# nodoSensorXbee_v3_2.net
KiCad netlist of a schematic drawn in EAGLE
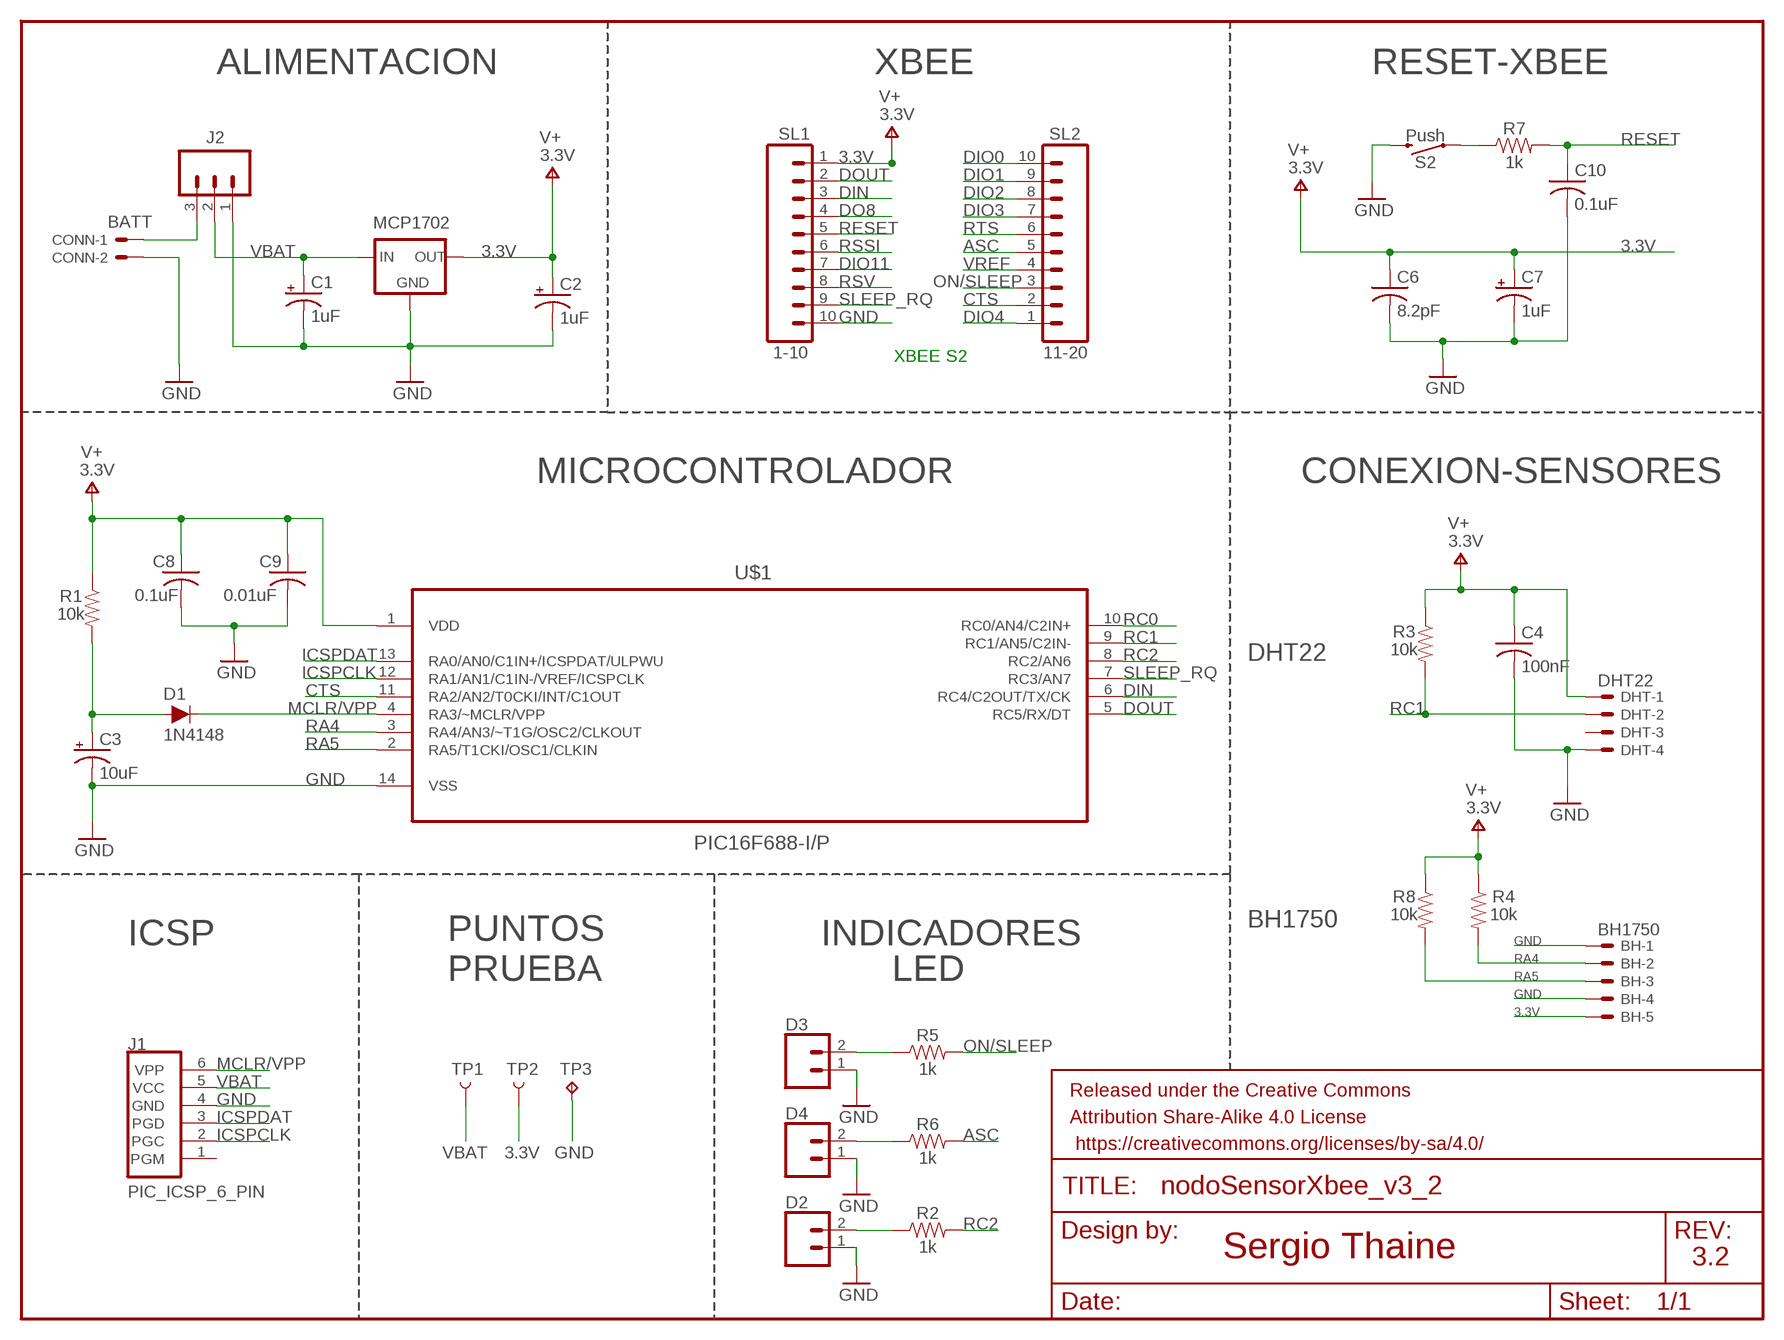
[diagram p0: schematic, sheet 1]

(export (version "E")
  (design (tool "Eeschema 10.0.6"))
  (components
    (comp (ref "BH")
      (value "BH1750")
      (footprint "eagle-import:6410-05")
      (libsource (lib "eagle-import") (part "22-?-0527-2051"))
    )
    (comp (ref "C1")
      (value "1uF")
      (footprint "eagle-import:E2-5")
      (libsource (lib "eagle-import") (part "CPOL-USE2-5"))
    )
    (comp (ref "C2")
      (value "1uF")
      (footprint "eagle-import:E2-5")
      (libsource (lib "eagle-import") (part "CPOL-USE2-5"))
    )
    (comp (ref "C3")
      (value "10uF")
      (footprint "eagle-import:E2-5")
      (libsource (lib "eagle-import") (part "CPOL-USE2-5"))
    )
    (comp (ref "C4")
      (value "100nF")
      (footprint "eagle-import:C025-030X050")
      (libsource (lib "eagle-import") (part "C-US025-030X050"))
    )
    (comp (ref "C6")
      (value "8.2pF")
      (footprint "eagle-import:C025-030X050")
      (libsource (lib "eagle-import") (part "C-US025-030X050"))
    )
    (comp (ref "C7")
      (value "1uF")
      (footprint "eagle-import:E2-5")
      (libsource (lib "eagle-import") (part "CPOL-USE2-5"))
    )
    (comp (ref "C8")
      (value "0.1uF")
      (footprint "eagle-import:C025-030X050")
      (libsource (lib "eagle-import") (part "C-US025-030X050"))
    )
    (comp (ref "C9")
      (value "0.01uF")
      (footprint "eagle-import:C025-030X050")
      (libsource (lib "eagle-import") (part "C-US025-030X050"))
    )
    (comp (ref "C10")
      (value "0.1uF")
      (footprint "eagle-import:C025-030X050")
      (libsource (lib "eagle-import") (part "C-US025-030X050"))
    )
    (comp (ref "CONN")
      (value "BATT")
      (footprint "eagle-import:6410-02")
      (libsource (lib "eagle-import") (part "22-?-0227-2021"))
    )
    (comp (ref "D1")
      (value "1N4148")
      (footprint "eagle-import:DIODE-1N4148")
      (libsource (lib "eagle-import") (part "DIODE-1N4148"))
    )
    (comp (ref "D2")
      (value "CONN_02POLAR")
      (footprint "eagle-import:MOLEX-1X2")
      (libsource (lib "eagle-import") (part "CONN_02POLAR"))
    )
    (comp (ref "D3")
      (value "CONN_02POLAR")
      (footprint "eagle-import:MOLEX-1X2")
      (libsource (lib "eagle-import") (part "CONN_02POLAR"))
    )
    (comp (ref "D4")
      (value "CONN_02POLAR")
      (footprint "eagle-import:MOLEX-1X2")
      (libsource (lib "eagle-import") (part "CONN_02POLAR"))
    )
    (comp (ref "DHT")
      (value "DHT22")
      (footprint "eagle-import:6410-04")
      (libsource (lib "eagle-import") (part "22-?-0427-2041"))
    )
    (comp (ref "FRAME1")
      (value "FRAME-LETTERNO_PACKAGE")
      (footprint "eagle-import:DUMMY")
      (fields (field (name "DESIGNER") "Nobody"))
      (libsource (lib "eagle-import") (part "FRAME-LETTERNO_PACKAGE"))
    )
    (comp (ref "J1")
      (value "PIC_ICSP_6_PIN")
      (footprint "eagle-import:MOLEX-1X6")
      (libsource (lib "eagle-import") (part "PIC_ICSP_6_PIN"))
    )
    (comp (ref "J2")
      (value "CONN_03POLAR")
      (footprint "eagle-import:MOLEX-1X3")
      (libsource (lib "eagle-import") (part "CONN_03POLAR"))
    )
    (comp (ref "MCP1702")
      (value "3.3v")
      (footprint "eagle-import:TO92")
      (libsource (lib "eagle-import") (part "MCP1700TRI"))
    )
    (comp (ref "R1")
      (value "10k")
      (footprint "eagle-import:AXIAL-0.3-KIT")
      (libsource (lib "eagle-import") (part "10KOHM-HORIZ_KIT-1/4W-1%"))
    )
    (comp (ref "R2")
      (value "1k")
      (footprint "eagle-import:AXIAL-0.3-KIT")
      (libsource (lib "eagle-import") (part "10KOHM-HORIZ_KIT-1/4W-1%"))
    )
    (comp (ref "R3")
      (value "10k")
      (footprint "eagle-import:AXIAL-0.3-KIT")
      (libsource (lib "eagle-import") (part "10KOHM-HORIZ_KIT-1/4W-1%"))
    )
    (comp (ref "R4")
      (value "10k")
      (footprint "eagle-import:AXIAL-0.3-KIT")
      (libsource (lib "eagle-import") (part "10KOHM-HORIZ_KIT-1/4W-1%"))
    )
    (comp (ref "R5")
      (value "1k")
      (footprint "eagle-import:AXIAL-0.3-KIT")
      (libsource (lib "eagle-import") (part "10KOHM-HORIZ_KIT-1/4W-1%"))
    )
    (comp (ref "R6")
      (value "1k")
      (footprint "eagle-import:AXIAL-0.3-KIT")
      (libsource (lib "eagle-import") (part "10KOHM-HORIZ_KIT-1/4W-1%"))
    )
    (comp (ref "R7")
      (value "1k")
      (footprint "eagle-import:AXIAL-0.3-KIT")
      (libsource (lib "eagle-import") (part "10KOHM-HORIZ_KIT-1/4W-1%"))
    )
    (comp (ref "R8")
      (value "10k")
      (footprint "eagle-import:AXIAL-0.3-KIT")
      (libsource (lib "eagle-import") (part "10KOHM-HORIZ_KIT-1/4W-1%"))
    )
    (comp (ref "S2")
      (value "Push")
      (footprint "eagle-import:TACTILE_SWITCH_PTH_6.0MM")
      (libsource (lib "eagle-import") (part "MOMENTARY-SWITCH-SPST-PTH-6.0MM"))
    )
    (comp (ref "SL1")
      (value "1-10")
      (footprint "eagle-import:10P")
      (libsource (lib "eagle-import") (part "M10"))
    )
    (comp (ref "SL2")
      (value "11-20")
      (footprint "eagle-import:10P")
      (libsource (lib "eagle-import") (part "M10"))
    )
    (comp (ref "TP1")
      (value "VBAT")
      (footprint "eagle-import:PAD.03X.05")
      (libsource (lib "eagle-import") (part "TEST-POINT3X5"))
    )
    (comp (ref "TP2")
      (value "3.3V")
      (footprint "eagle-import:PAD.03X.05")
      (libsource (lib "eagle-import") (part "TEST-POINT3X5"))
    )
    (comp (ref "TP3")
      (value "TPPAD1-13")
      (footprint "eagle-import:P1-13")
      (libsource (lib "eagle-import") (part "TPPAD1-13"))
    )
    (comp (ref "U$1")
      (value "PIC16F688-I/P")
      (footprint "eagle-import:DIP254P762X533-14")
      (libsource (lib "eagle-import") (part "PIC16F688-I/P"))
    )
  )
  (nets
    (net (code "1") (name "/ASC") (class "Default")
      (node (ref "R6") (pin "P$2") (pinfunction "2_P$2") (pintype "passive"))
      (node (ref "SL2") (pin "5") (pinfunction "5_5") (pintype "passive"))
    )
    (net (code "2") (name "/CTS") (class "Default")
      (node (ref "SL2") (pin "2") (pinfunction "2_2") (pintype "passive"))
      (node (ref "U$1") (pin "11") (pinfunction "RA2/AN2/T0CKI/INT/C1OUT_11") (pintype "bidirectional"))
    )
    (net (code "3") (name "/DIN") (class "Default")
      (node (ref "SL1") (pin "3") (pinfunction "3_3") (pintype "passive"))
      (node (ref "U$1") (pin "6") (pinfunction "RC4/C2OUT/TX/CK_6") (pintype "bidirectional"))
    )
    (net (code "4") (name "/DIO0") (class "Default")
      (node (ref "SL2") (pin "10") (pinfunction "10_10") (pintype "passive"))
    )
    (net (code "5") (name "/DIO1") (class "Default")
      (node (ref "SL2") (pin "9") (pinfunction "9_9") (pintype "passive"))
    )
    (net (code "6") (name "/DIO2") (class "Default")
      (node (ref "SL2") (pin "8") (pinfunction "8_8") (pintype "passive"))
    )
    (net (code "7") (name "/DIO3") (class "Default")
      (node (ref "SL2") (pin "7") (pinfunction "7_7") (pintype "passive"))
    )
    (net (code "8") (name "/DIO4") (class "Default")
      (node (ref "SL2") (pin "1") (pinfunction "1_1") (pintype "passive"))
    )
    (net (code "9") (name "/DIO11") (class "Default")
      (node (ref "SL1") (pin "7") (pinfunction "7_7") (pintype "passive"))
    )
    (net (code "10") (name "/DO8") (class "Default")
      (node (ref "SL1") (pin "4") (pinfunction "4_4") (pintype "passive"))
    )
    (net (code "11") (name "/DOUT") (class "Default")
      (node (ref "SL1") (pin "2") (pinfunction "2_2") (pintype "passive"))
      (node (ref "U$1") (pin "5") (pinfunction "RC5/RX/DT_5") (pintype "bidirectional"))
    )
    (net (code "12") (name "/ICSPCLK") (class "Default")
      (node (ref "J1") (pin "2") (pinfunction "PGC_2") (pintype "bidirectional"))
      (node (ref "U$1") (pin "12") (pinfunction "RA1/AN1/C1IN-/VREF/ICSPCLK_12") (pintype "bidirectional"))
    )
    (net (code "13") (name "/ICSPDAT") (class "Default")
      (node (ref "J1") (pin "3") (pinfunction "PGD_3") (pintype "bidirectional"))
      (node (ref "U$1") (pin "13") (pinfunction "RA0/AN0/C1IN+/ICSPDAT/ULPWU_13") (pintype "bidirectional"))
    )
    (net (code "14") (name "/MCLR{slash}VPP") (class "Default")
      (node (ref "D1") (pin "C") (pinfunction "C_C") (pintype "passive"))
      (node (ref "J1") (pin "6") (pinfunction "VPP_6") (pintype "bidirectional"))
      (node (ref "U$1") (pin "4") (pinfunction "RA3/~{MCLR/VPP}_4") (pintype "input"))
    )
    (net (code "15") (name "/ON{slash}SLEEP") (class "Default")
      (node (ref "R5") (pin "P$2") (pinfunction "2_P$2") (pintype "passive"))
      (node (ref "SL2") (pin "3") (pinfunction "3_3") (pintype "passive"))
    )
    (net (code "16") (name "/RA4") (class "Default")
      (node (ref "BH") (pin "2") (pinfunction "S_2") (pintype "passive"))
      (node (ref "R4") (pin "P$2") (pinfunction "2_P$2") (pintype "passive"))
      (node (ref "U$1") (pin "3") (pinfunction "RA4/AN3/~{T1G/OSC2/CLKOUT}_3") (pintype "bidirectional"))
    )
    (net (code "17") (name "/RA5") (class "Default")
      (node (ref "BH") (pin "3") (pinfunction "S_3") (pintype "passive"))
      (node (ref "R8") (pin "P$2") (pinfunction "2_P$2") (pintype "passive"))
      (node (ref "U$1") (pin "2") (pinfunction "RA5/T1CKI/OSC1/CLKIN_2") (pintype "bidirectional"))
    )
    (net (code "18") (name "/RC0") (class "Default")
      (node (ref "U$1") (pin "10") (pinfunction "RC0/AN4/C2IN+_10") (pintype "bidirectional"))
    )
    (net (code "19") (name "/RC1") (class "Default")
      (node (ref "DHT") (pin "2") (pinfunction "S_2") (pintype "passive"))
      (node (ref "R3") (pin "P$2") (pinfunction "2_P$2") (pintype "passive"))
      (node (ref "U$1") (pin "9") (pinfunction "RC1/AN5/C2IN-_9") (pintype "bidirectional"))
    )
    (net (code "20") (name "/RC2") (class "Default")
      (node (ref "R2") (pin "P$2") (pinfunction "2_P$2") (pintype "passive"))
      (node (ref "U$1") (pin "8") (pinfunction "RC2/AN6_8") (pintype "bidirectional"))
    )
    (net (code "21") (name "/RESET") (class "Default")
      (node (ref "C10") (pin "1") (pinfunction "1_1") (pintype "passive"))
      (node (ref "R7") (pin "P$2") (pinfunction "2_P$2") (pintype "passive"))
      (node (ref "SL1") (pin "5") (pinfunction "5_5") (pintype "passive"))
    )
    (net (code "22") (name "/RSSI") (class "Default")
      (node (ref "SL1") (pin "6") (pinfunction "6_6") (pintype "passive"))
    )
    (net (code "23") (name "/RSV") (class "Default")
      (node (ref "SL1") (pin "8") (pinfunction "8_8") (pintype "passive"))
    )
    (net (code "24") (name "/RTS") (class "Default")
      (node (ref "SL2") (pin "6") (pinfunction "6_6") (pintype "passive"))
    )
    (net (code "25") (name "/SLEEP_RQ") (class "Default")
      (node (ref "SL1") (pin "9") (pinfunction "9_9") (pintype "passive"))
      (node (ref "U$1") (pin "7") (pinfunction "RC3/AN7_7") (pintype "bidirectional"))
    )
    (net (code "26") (name "/VBAT") (class "Default")
      (node (ref "C1") (pin "+") (pinfunction "+_+") (pintype "passive"))
      (node (ref "J1") (pin "5") (pinfunction "VCC_5") (pintype "power_in"))
      (node (ref "J2") (pin "2") (pinfunction "2_2") (pintype "passive"))
      (node (ref "MCP1702") (pin "2") (pinfunction "IN_2") (pintype "input"))
      (node (ref "TP1") (pin "P$1") (pinfunction "1_P$1") (pintype "bidirectional"))
    )
    (net (code "27") (name "/VREF") (class "Default")
      (node (ref "SL2") (pin "4") (pinfunction "4_4") (pintype "passive"))
    )
    (net (code "28") (name "GND") (class "Default")
      (node (ref "BH") (pin "1") (pinfunction "S_1") (pintype "passive"))
      (node (ref "BH") (pin "4") (pinfunction "S_4") (pintype "passive"))
      (node (ref "C1") (pin "-") (pinfunction "-_-") (pintype "passive"))
      (node (ref "C10") (pin "2") (pinfunction "2_2") (pintype "passive"))
      (node (ref "C2") (pin "-") (pinfunction "-_-") (pintype "passive"))
      (node (ref "C3") (pin "-") (pinfunction "-_-") (pintype "passive"))
      (node (ref "C4") (pin "2") (pinfunction "2_2") (pintype "passive"))
      (node (ref "C6") (pin "2") (pinfunction "2_2") (pintype "passive"))
      (node (ref "C7") (pin "-") (pinfunction "-_-") (pintype "passive"))
      (node (ref "C8") (pin "2") (pinfunction "2_2") (pintype "passive"))
      (node (ref "C9") (pin "2") (pinfunction "2_2") (pintype "passive"))
      (node (ref "CONN") (pin "2") (pinfunction "S_2") (pintype "passive"))
      (node (ref "D2") (pin "1") (pinfunction "1_1") (pintype "passive"))
      (node (ref "D3") (pin "1") (pinfunction "1_1") (pintype "passive"))
      (node (ref "D4") (pin "1") (pinfunction "1_1") (pintype "passive"))
      (node (ref "DHT") (pin "4") (pinfunction "S_4") (pintype "passive"))
      (node (ref "J1") (pin "4") (pinfunction "GND_4") (pintype "power_in"))
      (node (ref "J2") (pin "1") (pinfunction "1_1") (pintype "passive"))
      (node (ref "MCP1702") (pin "1") (pinfunction "GND_1") (pintype "input"))
      (node (ref "S2") (pin "3") (pinfunction "2_3") (pintype "passive"))
      (node (ref "SL1") (pin "10") (pinfunction "10_10") (pintype "passive"))
      (node (ref "TP3") (pin "TP") (pinfunction "TP_TP") (pintype "input"))
      (node (ref "U$1") (pin "14") (pinfunction "VSS_14") (pintype "power_in"))
    )
    (net (code "29") (name "Net-(CONNA-S)") (class "Default")
      (node (ref "CONN") (pin "1") (pinfunction "S_1") (pintype "passive"))
      (node (ref "J2") (pin "3") (pinfunction "3_3") (pintype "passive"))
    )
    (net (code "30") (name "Net-(R1-2)") (class "Default")
      (node (ref "C3") (pin "+") (pinfunction "+_+") (pintype "passive"))
      (node (ref "D1") (pin "A") (pinfunction "A_A") (pintype "passive"))
      (node (ref "R1") (pin "P$2") (pinfunction "2_P$2") (pintype "passive"))
    )
    (net (code "31") (name "Net-(R2-1)") (class "Default")
      (node (ref "D2") (pin "2") (pinfunction "2_2") (pintype "passive"))
      (node (ref "R2") (pin "P$1") (pinfunction "1_P$1") (pintype "passive"))
    )
    (net (code "32") (name "Net-(R5-1)") (class "Default")
      (node (ref "D3") (pin "2") (pinfunction "2_2") (pintype "passive"))
      (node (ref "R5") (pin "P$1") (pinfunction "1_P$1") (pintype "passive"))
    )
    (net (code "33") (name "Net-(R6-1)") (class "Default")
      (node (ref "D4") (pin "2") (pinfunction "2_2") (pintype "passive"))
      (node (ref "R6") (pin "P$1") (pinfunction "1_P$1") (pintype "passive"))
    )
    (net (code "34") (name "Net-(R7-1)") (class "Default")
      (node (ref "R7") (pin "P$1") (pinfunction "1_P$1") (pintype "passive"))
      (node (ref "S2") (pin "1") (pinfunction "1_1") (pintype "passive"))
    )
    (net (code "35") (name "V+") (class "Default")
      (node (ref "BH") (pin "5") (pinfunction "S_5") (pintype "passive"))
      (node (ref "C2") (pin "+") (pinfunction "+_+") (pintype "passive"))
      (node (ref "C4") (pin "1") (pinfunction "1_1") (pintype "passive"))
      (node (ref "C6") (pin "1") (pinfunction "1_1") (pintype "passive"))
      (node (ref "C7") (pin "+") (pinfunction "+_+") (pintype "passive"))
      (node (ref "C8") (pin "1") (pinfunction "1_1") (pintype "passive"))
      (node (ref "C9") (pin "1") (pinfunction "1_1") (pintype "passive"))
      (node (ref "DHT") (pin "1") (pinfunction "S_1") (pintype "passive"))
      (node (ref "MCP1702") (pin "3") (pinfunction "OUT_3") (pintype "passive"))
      (node (ref "R1") (pin "P$1") (pinfunction "1_P$1") (pintype "passive"))
      (node (ref "R3") (pin "P$1") (pinfunction "1_P$1") (pintype "passive"))
      (node (ref "R4") (pin "P$1") (pinfunction "1_P$1") (pintype "passive"))
      (node (ref "R8") (pin "P$1") (pinfunction "1_P$1") (pintype "passive"))
      (node (ref "SL1") (pin "1") (pinfunction "1_1") (pintype "passive"))
      (node (ref "TP2") (pin "P$1") (pinfunction "1_P$1") (pintype "bidirectional"))
      (node (ref "U$1") (pin "1") (pinfunction "VDD_1") (pintype "power_in"))
    )
    (net (code "36") (name "unconnected-(DHTC-S-Pad3)") (class "Default")
      (node (ref "DHT") (pin "3") (pinfunction "S_3") (pintype "passive"))
    )
    (net (code "37") (name "unconnected-(J1-PGM-Pad1)") (class "Default")
      (node (ref "J1") (pin "1") (pinfunction "PGM_1") (pintype "bidirectional"))
    )
  )
)
